# RGBKeyboard.net
KiCad netlist of a schematic drawn in EAGLE
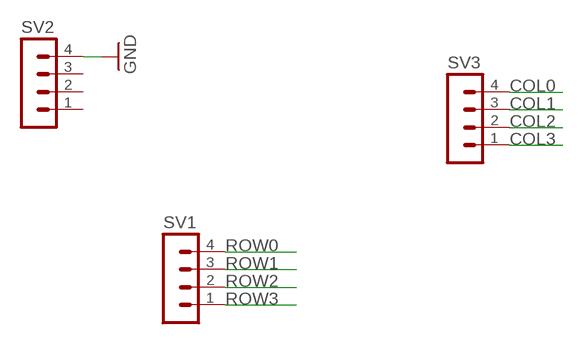
[diagram p0: schematic, sheet 1]
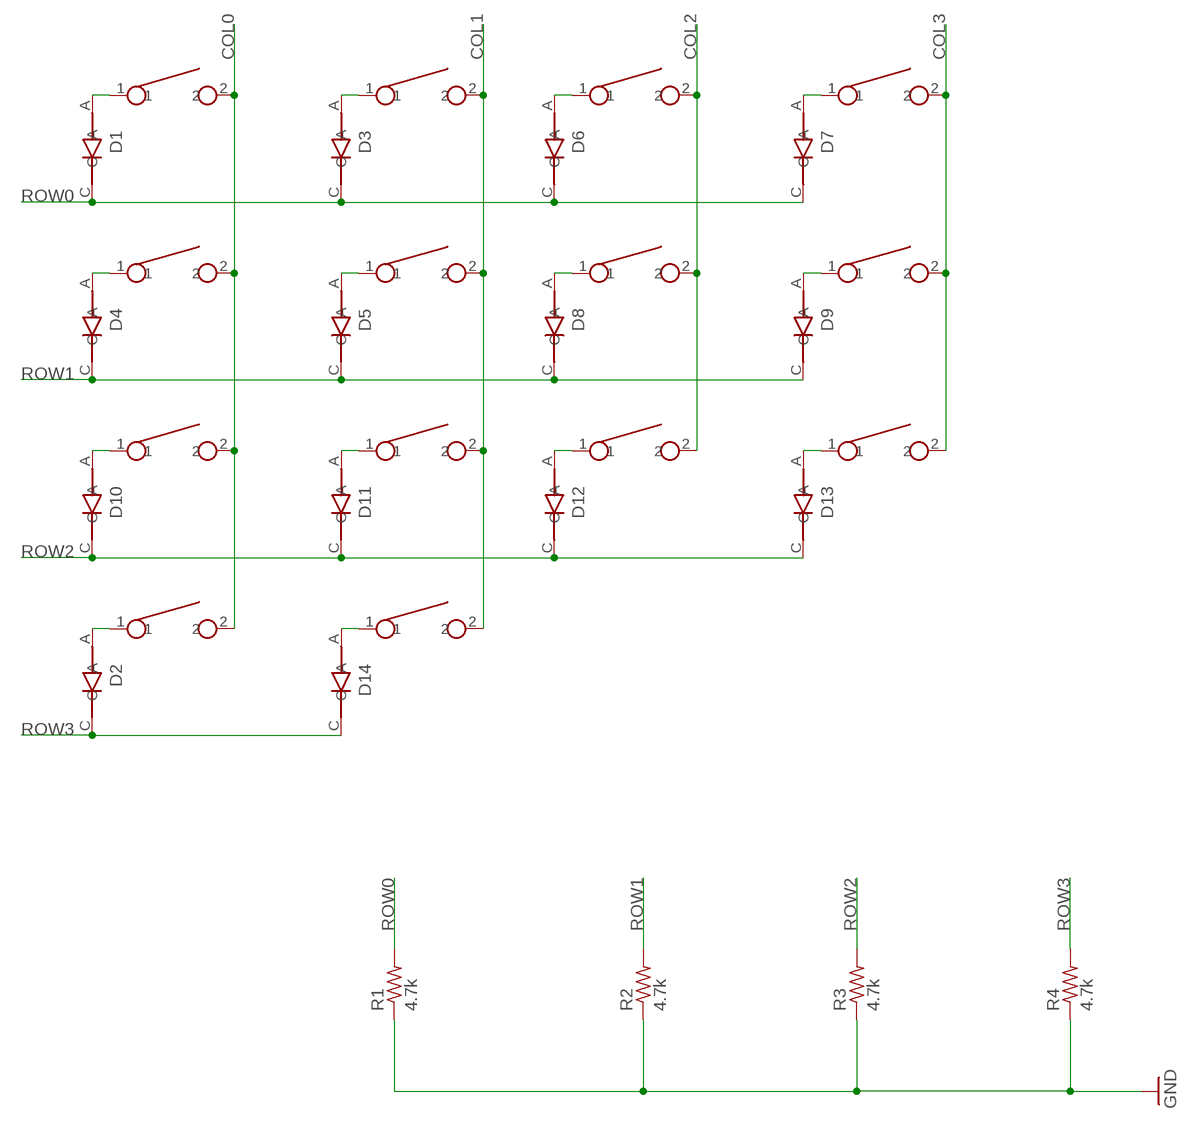
[diagram p1: schematic, sheet 2]

(export (version "E")
  (design (tool "Eeschema 10.0.6"))
  (components
    (comp (ref "SV1")
      (value "MA04-1")
      (footprint "eagle-import:MA04-1")
      (libsource (lib "eagle-import") (part "MA04-1"))
    )
    (comp (ref "SV2")
      (value "MA04-1")
      (footprint "eagle-import:MA04-1")
      (libsource (lib "eagle-import") (part "MA04-1"))
    )
    (comp (ref "SV3")
      (value "MA04-1")
      (footprint "eagle-import:MA04-1")
      (libsource (lib "eagle-import") (part "MA04-1"))
    )
    (comp (ref "D1")
      (value "BAV21W-7-F")
      (footprint "eagle-import:SOD3715X135N")
      (fields (field (name "DIGI-KEY_PART_NUMBER") "BAV21W-FDICT-ND") (field (name "MF") "Diodes Inc."))
      (libsource (lib "eagle-import") (part "BAV21W-7-F"))
    )
    (comp (ref "D2")
      (value "BAV21W-7-F")
      (footprint "eagle-import:SOD3715X135N")
      (fields (field (name "DIGI-KEY_PART_NUMBER") "BAV21W-FDICT-ND") (field (name "MF") "Diodes Inc."))
      (libsource (lib "eagle-import") (part "BAV21W-7-F"))
    )
    (comp (ref "D3")
      (value "BAV21W-7-F")
      (footprint "eagle-import:SOD3715X135N")
      (fields (field (name "DIGI-KEY_PART_NUMBER") "BAV21W-FDICT-ND") (field (name "MF") "Diodes Inc."))
      (libsource (lib "eagle-import") (part "BAV21W-7-F"))
    )
    (comp (ref "D4")
      (value "BAV21W-7-F")
      (footprint "eagle-import:SOD3715X135N")
      (fields (field (name "DIGI-KEY_PART_NUMBER") "BAV21W-FDICT-ND") (field (name "MF") "Diodes Inc."))
      (libsource (lib "eagle-import") (part "BAV21W-7-F"))
    )
    (comp (ref "D5")
      (value "BAV21W-7-F")
      (footprint "eagle-import:SOD3715X135N")
      (fields (field (name "DIGI-KEY_PART_NUMBER") "BAV21W-FDICT-ND") (field (name "MF") "Diodes Inc."))
      (libsource (lib "eagle-import") (part "BAV21W-7-F"))
    )
    (comp (ref "D6")
      (value "BAV21W-7-F")
      (footprint "eagle-import:SOD3715X135N")
      (fields (field (name "DIGI-KEY_PART_NUMBER") "BAV21W-FDICT-ND") (field (name "MF") "Diodes Inc."))
      (libsource (lib "eagle-import") (part "BAV21W-7-F"))
    )
    (comp (ref "D7")
      (value "BAV21W-7-F")
      (footprint "eagle-import:SOD3715X135N")
      (fields (field (name "DIGI-KEY_PART_NUMBER") "BAV21W-FDICT-ND") (field (name "MF") "Diodes Inc."))
      (libsource (lib "eagle-import") (part "BAV21W-7-F"))
    )
    (comp (ref "D8")
      (value "BAV21W-7-F")
      (footprint "eagle-import:SOD3715X135N")
      (fields (field (name "DIGI-KEY_PART_NUMBER") "BAV21W-FDICT-ND") (field (name "MF") "Diodes Inc."))
      (libsource (lib "eagle-import") (part "BAV21W-7-F"))
    )
    (comp (ref "D9")
      (value "BAV21W-7-F")
      (footprint "eagle-import:SOD3715X135N")
      (fields (field (name "DIGI-KEY_PART_NUMBER") "BAV21W-FDICT-ND") (field (name "MF") "Diodes Inc."))
      (libsource (lib "eagle-import") (part "BAV21W-7-F"))
    )
    (comp (ref "D10")
      (value "BAV21W-7-F")
      (footprint "eagle-import:SOD3715X135N")
      (fields (field (name "DIGI-KEY_PART_NUMBER") "BAV21W-FDICT-ND") (field (name "MF") "Diodes Inc."))
      (libsource (lib "eagle-import") (part "BAV21W-7-F"))
    )
    (comp (ref "D11")
      (value "BAV21W-7-F")
      (footprint "eagle-import:SOD3715X135N")
      (fields (field (name "DIGI-KEY_PART_NUMBER") "BAV21W-FDICT-ND") (field (name "MF") "Diodes Inc."))
      (libsource (lib "eagle-import") (part "BAV21W-7-F"))
    )
    (comp (ref "D12")
      (value "BAV21W-7-F")
      (footprint "eagle-import:SOD3715X135N")
      (fields (field (name "DIGI-KEY_PART_NUMBER") "BAV21W-FDICT-ND") (field (name "MF") "Diodes Inc."))
      (libsource (lib "eagle-import") (part "BAV21W-7-F"))
    )
    (comp (ref "D13")
      (value "BAV21W-7-F")
      (footprint "eagle-import:SOD3715X135N")
      (fields (field (name "DIGI-KEY_PART_NUMBER") "BAV21W-FDICT-ND") (field (name "MF") "Diodes Inc."))
      (libsource (lib "eagle-import") (part "BAV21W-7-F"))
    )
    (comp (ref "D14")
      (value "BAV21W-7-F")
      (footprint "eagle-import:SOD3715X135N")
      (fields (field (name "DIGI-KEY_PART_NUMBER") "BAV21W-FDICT-ND") (field (name "MF") "Diodes Inc."))
      (libsource (lib "eagle-import") (part "BAV21W-7-F"))
    )
    (comp (ref "R1")
      (value "4.7k")
      (footprint "eagle-import:R0603")
      (libsource (lib "eagle-import") (part "R-US_R0603"))
    )
    (comp (ref "R2")
      (value "4.7k")
      (footprint "eagle-import:R0603")
      (libsource (lib "eagle-import") (part "R-US_R0603"))
    )
    (comp (ref "R3")
      (value "4.7k")
      (footprint "eagle-import:R0603")
      (libsource (lib "eagle-import") (part "R-US_R0603"))
    )
    (comp (ref "R4")
      (value "4.7k")
      (footprint "eagle-import:R0603")
      (libsource (lib "eagle-import") (part "R-US_R0603"))
    )
    (comp (ref "U$1")
      (value "CHERRY_MX")
      (footprint "eagle-import:CHERRY_MX")
      (libsource (lib "eagle-import") (part "CHERRY_MX"))
    )
    (comp (ref "U$2")
      (value "CHERRY_MX")
      (footprint "eagle-import:CHERRY_MX")
      (libsource (lib "eagle-import") (part "CHERRY_MX"))
    )
    (comp (ref "U$3")
      (value "CHERRY_MX")
      (footprint "eagle-import:CHERRY_MX")
      (libsource (lib "eagle-import") (part "CHERRY_MX"))
    )
    (comp (ref "U$4")
      (value "CHERRY_MX")
      (footprint "eagle-import:CHERRY_MX")
      (libsource (lib "eagle-import") (part "CHERRY_MX"))
    )
    (comp (ref "U$5")
      (value "CHERRY_MX")
      (footprint "eagle-import:CHERRY_MX")
      (libsource (lib "eagle-import") (part "CHERRY_MX"))
    )
    (comp (ref "U$6")
      (value "CHERRY_MX")
      (footprint "eagle-import:CHERRY_MX")
      (libsource (lib "eagle-import") (part "CHERRY_MX"))
    )
    (comp (ref "U$7")
      (value "CHERRY_MX")
      (footprint "eagle-import:CHERRY_MX")
      (libsource (lib "eagle-import") (part "CHERRY_MX"))
    )
    (comp (ref "U$8")
      (value "CHERRY_MX")
      (footprint "eagle-import:CHERRY_MX")
      (libsource (lib "eagle-import") (part "CHERRY_MX"))
    )
    (comp (ref "U$9")
      (value "CHERRY_MX")
      (footprint "eagle-import:CHERRY_MX")
      (libsource (lib "eagle-import") (part "CHERRY_MX"))
    )
    (comp (ref "U$10")
      (value "CHERRY_MX")
      (footprint "eagle-import:CHERRY_MX")
      (libsource (lib "eagle-import") (part "CHERRY_MX"))
    )
    (comp (ref "U$11")
      (value "CHERRY_MX")
      (footprint "eagle-import:CHERRY_MX")
      (libsource (lib "eagle-import") (part "CHERRY_MX"))
    )
    (comp (ref "U$12")
      (value "CHERRY_MX")
      (footprint "eagle-import:CHERRY_MX")
      (libsource (lib "eagle-import") (part "CHERRY_MX"))
    )
    (comp (ref "U$13")
      (value "CHERRY_MXCHERRY_MX_1_2")
      (footprint "eagle-import:CHERRY_MX_1_2")
      (libsource (lib "eagle-import") (part "CHERRY_MXCHERRY_MX_1_2"))
    )
    (comp (ref "U$14")
      (value "CHERRY_MXCHERRY_MX_1_2")
      (footprint "eagle-import:CHERRY_MX_1_2")
      (libsource (lib "eagle-import") (part "CHERRY_MXCHERRY_MX_1_2"))
    )
  )
  (nets
    (net (code "1") (name "COL0") (class "Default")
      (node (ref "SV3") (pin "4") (pinfunction "4_4") (pintype "passive"))
      (node (ref "U$1") (pin "2") (pinfunction "2_2") (pintype "bidirectional"))
      (node (ref "U$13") (pin "2") (pinfunction "2_2") (pintype "bidirectional"))
      (node (ref "U$2") (pin "2") (pinfunction "2_2") (pintype "bidirectional"))
      (node (ref "U$3") (pin "2") (pinfunction "2_2") (pintype "bidirectional"))
    )
    (net (code "2") (name "COL1") (class "Default")
      (node (ref "SV3") (pin "3") (pinfunction "3_3") (pintype "passive"))
      (node (ref "U$14") (pin "2") (pinfunction "2_2") (pintype "bidirectional"))
      (node (ref "U$4") (pin "2") (pinfunction "2_2") (pintype "bidirectional"))
      (node (ref "U$5") (pin "2") (pinfunction "2_2") (pintype "bidirectional"))
      (node (ref "U$6") (pin "2") (pinfunction "2_2") (pintype "bidirectional"))
    )
    (net (code "3") (name "COL2") (class "Default")
      (node (ref "SV3") (pin "2") (pinfunction "2_2") (pintype "passive"))
      (node (ref "U$7") (pin "2") (pinfunction "2_2") (pintype "bidirectional"))
      (node (ref "U$8") (pin "2") (pinfunction "2_2") (pintype "bidirectional"))
      (node (ref "U$9") (pin "2") (pinfunction "2_2") (pintype "bidirectional"))
    )
    (net (code "4") (name "COL3") (class "Default")
      (node (ref "SV3") (pin "1") (pinfunction "1_1") (pintype "passive"))
      (node (ref "U$10") (pin "2") (pinfunction "2_2") (pintype "bidirectional"))
      (node (ref "U$11") (pin "2") (pinfunction "2_2") (pintype "bidirectional"))
      (node (ref "U$12") (pin "2") (pinfunction "2_2") (pintype "bidirectional"))
    )
    (net (code "5") (name "GND") (class "Default")
      (node (ref "R1") (pin "1") (pinfunction "1_1") (pintype "passive"))
      (node (ref "R2") (pin "1") (pinfunction "1_1") (pintype "passive"))
      (node (ref "R3") (pin "1") (pinfunction "1_1") (pintype "passive"))
      (node (ref "R4") (pin "1") (pinfunction "1_1") (pintype "passive"))
      (node (ref "SV2") (pin "4") (pinfunction "4_4") (pintype "passive"))
    )
    (net (code "6") (name "Net-(D1-PadA)") (class "Default")
      (node (ref "D1") (pin "A") (pinfunction "A_A") (pintype "passive"))
      (node (ref "U$1") (pin "1") (pinfunction "1_1") (pintype "bidirectional"))
    )
    (net (code "7") (name "Net-(D2-PadA)") (class "Default")
      (node (ref "D2") (pin "A") (pinfunction "A_A") (pintype "passive"))
      (node (ref "U$13") (pin "1") (pinfunction "1_1") (pintype "bidirectional"))
    )
    (net (code "8") (name "Net-(D3-PadA)") (class "Default")
      (node (ref "D3") (pin "A") (pinfunction "A_A") (pintype "passive"))
      (node (ref "U$4") (pin "1") (pinfunction "1_1") (pintype "bidirectional"))
    )
    (net (code "9") (name "Net-(D4-PadA)") (class "Default")
      (node (ref "D4") (pin "A") (pinfunction "A_A") (pintype "passive"))
      (node (ref "U$2") (pin "1") (pinfunction "1_1") (pintype "bidirectional"))
    )
    (net (code "10") (name "Net-(D5-PadA)") (class "Default")
      (node (ref "D5") (pin "A") (pinfunction "A_A") (pintype "passive"))
      (node (ref "U$5") (pin "1") (pinfunction "1_1") (pintype "bidirectional"))
    )
    (net (code "11") (name "Net-(D6-PadA)") (class "Default")
      (node (ref "D6") (pin "A") (pinfunction "A_A") (pintype "passive"))
      (node (ref "U$7") (pin "1") (pinfunction "1_1") (pintype "bidirectional"))
    )
    (net (code "12") (name "Net-(D7-PadA)") (class "Default")
      (node (ref "D7") (pin "A") (pinfunction "A_A") (pintype "passive"))
      (node (ref "U$12") (pin "1") (pinfunction "1_1") (pintype "bidirectional"))
    )
    (net (code "13") (name "Net-(D8-PadA)") (class "Default")
      (node (ref "D8") (pin "A") (pinfunction "A_A") (pintype "passive"))
      (node (ref "U$8") (pin "1") (pinfunction "1_1") (pintype "bidirectional"))
    )
    (net (code "14") (name "Net-(D9-PadA)") (class "Default")
      (node (ref "D9") (pin "A") (pinfunction "A_A") (pintype "passive"))
      (node (ref "U$10") (pin "1") (pinfunction "1_1") (pintype "bidirectional"))
    )
    (net (code "15") (name "Net-(D10-PadA)") (class "Default")
      (node (ref "D10") (pin "A") (pinfunction "A_A") (pintype "passive"))
      (node (ref "U$3") (pin "1") (pinfunction "1_1") (pintype "bidirectional"))
    )
    (net (code "16") (name "Net-(D11-PadA)") (class "Default")
      (node (ref "D11") (pin "A") (pinfunction "A_A") (pintype "passive"))
      (node (ref "U$6") (pin "1") (pinfunction "1_1") (pintype "bidirectional"))
    )
    (net (code "17") (name "Net-(D12-PadA)") (class "Default")
      (node (ref "D12") (pin "A") (pinfunction "A_A") (pintype "passive"))
      (node (ref "U$9") (pin "1") (pinfunction "1_1") (pintype "bidirectional"))
    )
    (net (code "18") (name "Net-(D13-PadA)") (class "Default")
      (node (ref "D13") (pin "A") (pinfunction "A_A") (pintype "passive"))
      (node (ref "U$11") (pin "1") (pinfunction "1_1") (pintype "bidirectional"))
    )
    (net (code "19") (name "Net-(D14-PadA)") (class "Default")
      (node (ref "D14") (pin "A") (pinfunction "A_A") (pintype "passive"))
      (node (ref "U$14") (pin "1") (pinfunction "1_1") (pintype "bidirectional"))
    )
    (net (code "20") (name "ROW0") (class "Default")
      (node (ref "D1") (pin "C") (pinfunction "C_C") (pintype "passive"))
      (node (ref "D3") (pin "C") (pinfunction "C_C") (pintype "passive"))
      (node (ref "D6") (pin "C") (pinfunction "C_C") (pintype "passive"))
      (node (ref "D7") (pin "C") (pinfunction "C_C") (pintype "passive"))
      (node (ref "R1") (pin "2") (pinfunction "2_2") (pintype "passive"))
      (node (ref "SV1") (pin "4") (pinfunction "4_4") (pintype "passive"))
    )
    (net (code "21") (name "ROW1") (class "Default")
      (node (ref "D4") (pin "C") (pinfunction "C_C") (pintype "passive"))
      (node (ref "D5") (pin "C") (pinfunction "C_C") (pintype "passive"))
      (node (ref "D8") (pin "C") (pinfunction "C_C") (pintype "passive"))
      (node (ref "D9") (pin "C") (pinfunction "C_C") (pintype "passive"))
      (node (ref "R2") (pin "2") (pinfunction "2_2") (pintype "passive"))
      (node (ref "SV1") (pin "3") (pinfunction "3_3") (pintype "passive"))
    )
    (net (code "22") (name "ROW2") (class "Default")
      (node (ref "D10") (pin "C") (pinfunction "C_C") (pintype "passive"))
      (node (ref "D11") (pin "C") (pinfunction "C_C") (pintype "passive"))
      (node (ref "D12") (pin "C") (pinfunction "C_C") (pintype "passive"))
      (node (ref "D13") (pin "C") (pinfunction "C_C") (pintype "passive"))
      (node (ref "R3") (pin "2") (pinfunction "2_2") (pintype "passive"))
      (node (ref "SV1") (pin "2") (pinfunction "2_2") (pintype "passive"))
    )
    (net (code "23") (name "ROW3") (class "Default")
      (node (ref "D14") (pin "C") (pinfunction "C_C") (pintype "passive"))
      (node (ref "D2") (pin "C") (pinfunction "C_C") (pintype "passive"))
      (node (ref "R4") (pin "2") (pinfunction "2_2") (pintype "passive"))
      (node (ref "SV1") (pin "1") (pinfunction "1_1") (pintype "passive"))
    )
    (net (code "24") (name "unconnected-(SV2-Pad1)") (class "Default")
      (node (ref "SV2") (pin "1") (pinfunction "1_1") (pintype "passive"))
    )
    (net (code "25") (name "unconnected-(SV2-Pad2)") (class "Default")
      (node (ref "SV2") (pin "2") (pinfunction "2_2") (pintype "passive"))
    )
    (net (code "26") (name "unconnected-(SV2-Pad3)") (class "Default")
      (node (ref "SV2") (pin "3") (pinfunction "3_3") (pintype "passive"))
    )
  )
)
